# usblipocharger-own_-_Kopie.net
KiCad netlist of a schematic drawn in EAGLE
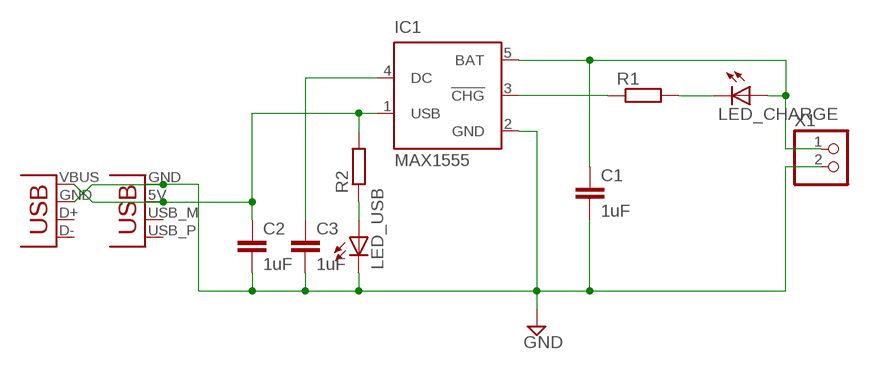
[diagram p0: schematic, sheet 1]

(export (version "E")
  (design (tool "Eeschema 10.0.6"))
  (components
    (comp (ref "C1")
      (value "1uF")
      (footprint "eagle-import:C0805")
      (libsource (lib "eagle-import") (part "C-EUC0805"))
    )
    (comp (ref "C2")
      (value "1uF")
      (footprint "eagle-import:C0805")
      (libsource (lib "eagle-import") (part "C-EUC0805"))
    )
    (comp (ref "C3")
      (value "1uF")
      (footprint "eagle-import:C0805")
      (libsource (lib "eagle-import") (part "C-EUC0805"))
    )
    (comp (ref "IC1")
      (value "MAX1555")
      (footprint "eagle-import:SOT23-5L")
      (libsource (lib "eagle-import") (part "MAX1555"))
    )
    (comp (ref "JP1")
      (value "USBPCB")
      (footprint "eagle-import:USB-A-PCB")
      (libsource (lib "eagle-import") (part "USBPCB"))
    )
    (comp (ref "JP2")
      (value "USB-A-H")
      (footprint "eagle-import:USB-A-H")
      (libsource (lib "eagle-import") (part "USB-A-H"))
    )
    (comp (ref "LED_CHARGE")
      (value "LEDCHIP-LED0805")
      (footprint "eagle-import:CHIP-LED0805")
      (libsource (lib "eagle-import") (part "LEDCHIP-LED0805"))
    )
    (comp (ref "LED_USB")
      (value "LEDCHIP-LED0805")
      (footprint "eagle-import:CHIP-LED0805")
      (libsource (lib "eagle-import") (part "LEDCHIP-LED0805"))
    )
    (comp (ref "R1")
      (value "R-EU_R0805")
      (footprint "eagle-import:R0805")
      (libsource (lib "eagle-import") (part "R-EU_R0805"))
    )
    (comp (ref "R2")
      (value "R-EU_R0805")
      (footprint "eagle-import:R0805")
      (libsource (lib "eagle-import") (part "R-EU_R0805"))
    )
    (comp (ref "X1")
      (value "PINHD-1X2")
      (footprint "eagle-import:1X02")
      (libsource (lib "eagle-import") (part "PINHD-1X2"))
    )
  )
  (nets
    (net (code "1") (name "GND") (class "Default")
      (node (ref "C1") (pin "2") (pinfunction "2_2") (pintype "passive"))
      (node (ref "C2") (pin "2") (pinfunction "2_2") (pintype "passive"))
      (node (ref "C3") (pin "2") (pinfunction "2_2") (pintype "passive"))
      (node (ref "IC1") (pin "2") (pinfunction "GND_2") (pintype "power_in"))
      (node (ref "JP1") (pin "GND") (pinfunction "GND_GND") (pintype "bidirectional"))
      (node (ref "JP2") (pin "GND") (pinfunction "VBUS_GND") (pintype "bidirectional"))
      (node (ref "LED_USB") (pin "C") (pinfunction "C_C") (pintype "passive"))
      (node (ref "X1") (pin "2") (pinfunction "2_2") (pintype "passive"))
    )
    (net (code "2") (name "Net-(IC1-BAT)") (class "Default")
      (node (ref "C1") (pin "1") (pinfunction "1_1") (pintype "passive"))
      (node (ref "IC1") (pin "5") (pinfunction "BAT_5") (pintype "passive"))
      (node (ref "LED_CHARGE") (pin "A") (pinfunction "A_A") (pintype "passive"))
      (node (ref "X1") (pin "1") (pinfunction "1_1") (pintype "passive"))
    )
    (net (code "3") (name "Net-(IC1-DC)") (class "Default")
      (node (ref "C3") (pin "1") (pinfunction "1_1") (pintype "passive"))
      (node (ref "IC1") (pin "4") (pinfunction "DC_4") (pintype "input"))
    )
    (net (code "4") (name "Net-(IC1-USB)") (class "Default")
      (node (ref "C2") (pin "1") (pinfunction "1_1") (pintype "passive"))
      (node (ref "IC1") (pin "1") (pinfunction "USB_1") (pintype "input"))
      (node (ref "JP1") (pin "5V") (pinfunction "VBUS_5V") (pintype "bidirectional"))
      (node (ref "JP2") (pin "VBUS") (pinfunction "GND_VBUS") (pintype "bidirectional"))
      (node (ref "R2") (pin "2") (pinfunction "2_2") (pintype "passive"))
    )
    (net (code "5") (name "Net-(IC1-~{CHG})") (class "Default")
      (node (ref "IC1") (pin "3") (pinfunction "~{CHG}_3") (pintype "output"))
      (node (ref "R1") (pin "1") (pinfunction "1_1") (pintype "passive"))
    )
    (net (code "6") (name "Net-(LED_CHARGE-PadC)") (class "Default")
      (node (ref "LED_CHARGE") (pin "C") (pinfunction "C_C") (pintype "passive"))
      (node (ref "R1") (pin "2") (pinfunction "2_2") (pintype "passive"))
    )
    (net (code "7") (name "Net-(LED_USB-PadA)") (class "Default")
      (node (ref "LED_USB") (pin "A") (pinfunction "A_A") (pintype "passive"))
      (node (ref "R2") (pin "1") (pinfunction "1_1") (pintype "passive"))
    )
    (net (code "8") (name "unconnected-(JP1-D+-PadUSB_P)") (class "Default")
      (node (ref "JP1") (pin "USB_P") (pinfunction "D+_USB_P") (pintype "bidirectional"))
    )
    (net (code "9") (name "unconnected-(JP1-D--PadUSB_M)") (class "Default")
      (node (ref "JP1") (pin "USB_M") (pinfunction "D-_USB_M") (pintype "bidirectional"))
    )
    (net (code "10") (name "unconnected-(JP2-D+-PadD-)") (class "Default")
      (node (ref "JP2") (pin "D-") (pinfunction "D+_D-") (pintype "bidirectional"))
    )
    (net (code "11") (name "unconnected-(JP2-D--PadD+)") (class "Default")
      (node (ref "JP2") (pin "D+") (pinfunction "D-_D+") (pintype "bidirectional"))
    )
  )
)
